# ball_catch_sensor_2.net
KiCad netlist of a schematic drawn in EAGLE
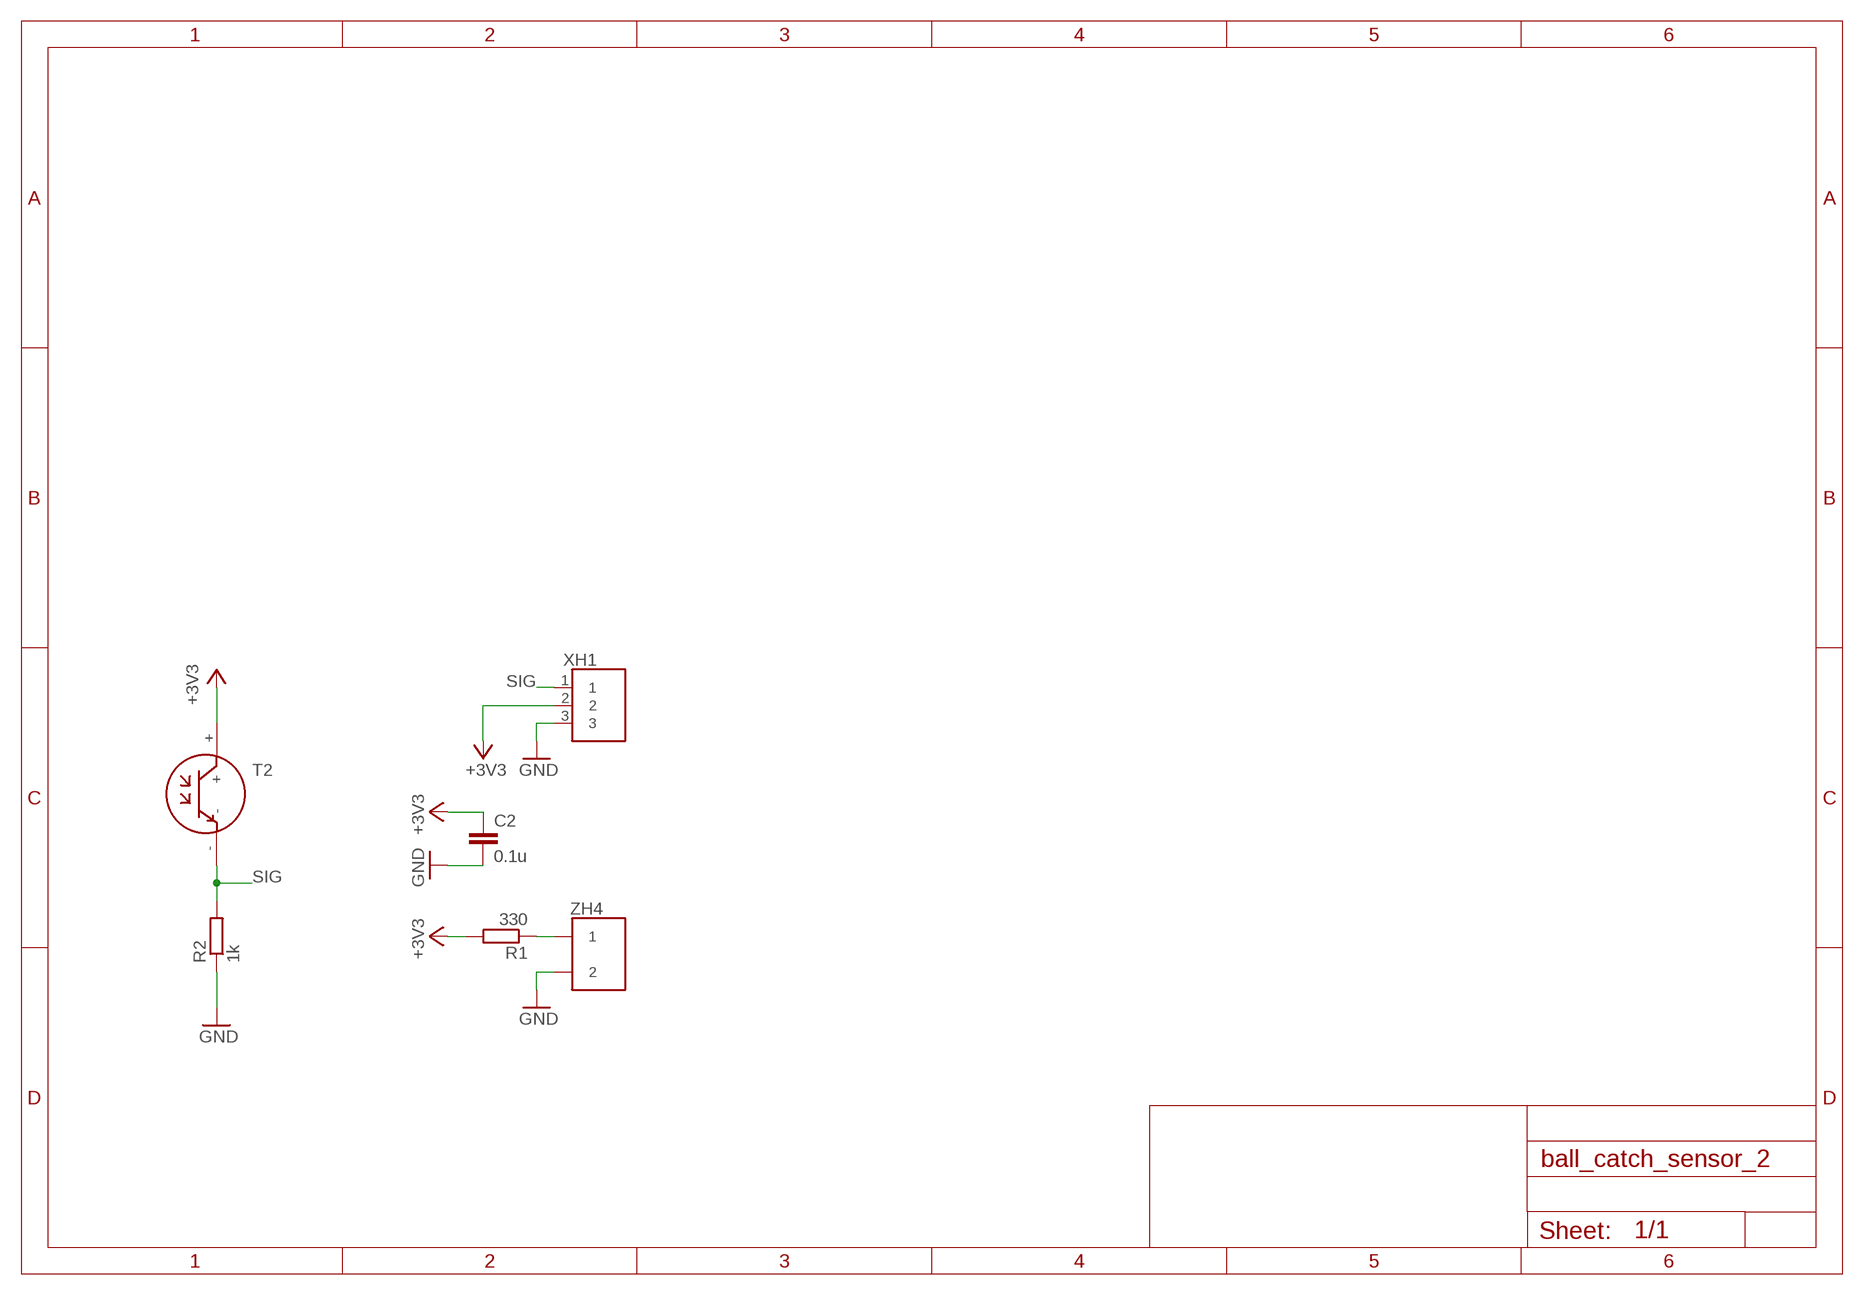
[diagram p0: schematic, sheet 1]

(export (version "E")
  (design (tool "Eeschema 10.0.6"))
  (components
    (comp (ref "C2")
      (value "0.1u")
      (footprint "eagle-import:C0603")
      (libsource (lib "eagle-import") (part "C-EUC0603"))
    )
    (comp (ref "R1")
      (value "330")
      (footprint "eagle-import:0207_10")
      (libsource (lib "eagle-import") (part "R-EU_0207/10"))
    )
    (comp (ref "R2")
      (value "1k")
      (footprint "eagle-import:0207_10")
      (libsource (lib "eagle-import") (part "R-EU_0207/10"))
    )
    (comp (ref "T2")
      (value "NJL7302L-F3")
      (footprint "eagle-import:NJL7302L-F3")
      (libsource (lib "eagle-import") (part "NJL7302L-F3"))
    )
    (comp (ref "XH1")
      (value "S3B")
      (footprint "eagle-import:S3B")
      (libsource (lib "eagle-import") (part "S3B"))
    )
    (comp (ref "ZH4") (value "2B") (footprint "eagle-import:2B") (libsource (lib "eagle-import") (part "2B")))
  )
  (nets
    (net (code "1") (name "+3V3") (class "Default")
      (node (ref "C2") (pin "1") (pinfunction "1_1") (pintype "passive"))
      (node (ref "R1") (pin "2") (pinfunction "2_2") (pintype "passive"))
      (node (ref "T2") (pin "+") (pinfunction "+_+") (pintype "bidirectional"))
      (node (ref "XH1") (pin "2") (pinfunction "2_2") (pintype "bidirectional"))
    )
    (net (code "2") (name "/SIG") (class "Default")
      (node (ref "R2") (pin "2") (pinfunction "2_2") (pintype "passive"))
      (node (ref "T2") (pin "-") (pinfunction "-_-") (pintype "bidirectional"))
      (node (ref "XH1") (pin "1") (pinfunction "1_1") (pintype "bidirectional"))
    )
    (net (code "3") (name "GND") (class "Default")
      (node (ref "C2") (pin "2") (pinfunction "2_2") (pintype "passive"))
      (node (ref "R2") (pin "1") (pinfunction "1_1") (pintype "passive"))
      (node (ref "XH1") (pin "3") (pinfunction "3_3") (pintype "bidirectional"))
      (node (ref "ZH4") (pin "2") (pinfunction "2_2") (pintype "bidirectional"))
    )
    (net (code "4") (name "Net-(R1-Pad1)") (class "Default")
      (node (ref "R1") (pin "1") (pinfunction "1_1") (pintype "passive"))
      (node (ref "ZH4") (pin "1") (pinfunction "1_1") (pintype "bidirectional"))
    )
  )
)
